# SparkFun_Qwiic_Mini_Human_Presence_Senso.net
KiCad netlist of a schematic drawn in EAGLE
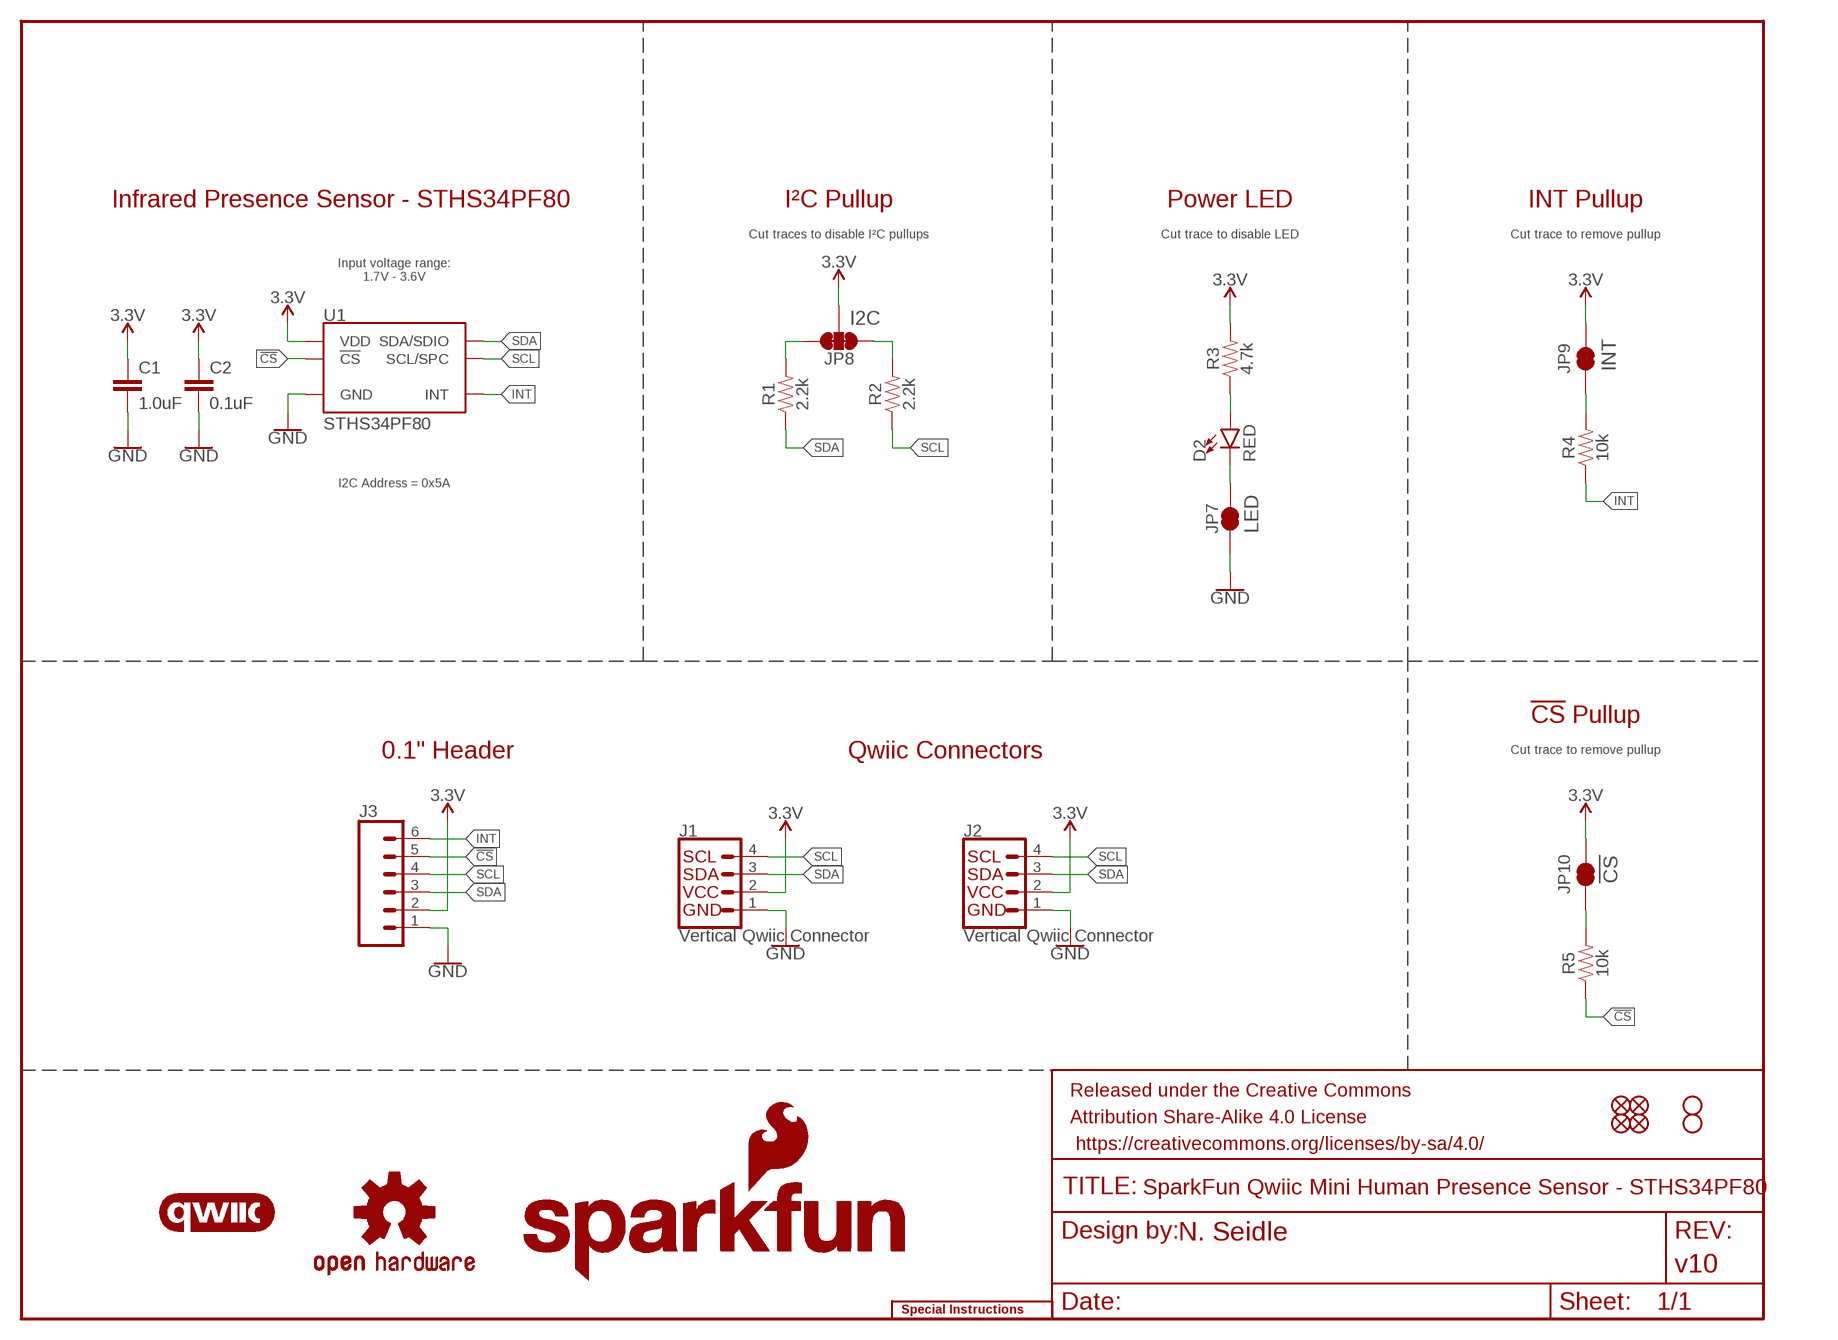
[diagram p0: schematic, sheet 1]

(export (version "E")
  (design (tool "Eeschema 10.0.6"))
  (components
    (comp (ref "C1")
      (value "1.0uF")
      (footprint "eagle-import:0603")
      (libsource (lib "eagle-import") (part "1.0UF-0603-16V-10%"))
    )
    (comp (ref "C2")
      (value "0.1uF")
      (footprint "eagle-import:0603")
      (libsource (lib "eagle-import") (part "0.1UF-0603-25V-(+80/-20%)"))
    )
    (comp (ref "D2")
      (value "RED")
      (footprint "eagle-import:LED-0603")
      (libsource (lib "eagle-import") (part "LED-RED_0603-KB"))
    )
    (comp (ref "FRAME1")
      (value "FRAME-LETTER")
      (footprint "eagle-import:CREATIVE_COMMONS")
      (fields (field (name "DESIGNER") "N. Seidle") (field (name "REV") "v10"))
      (libsource (lib "eagle-import") (part "FRAME-LETTER"))
    )
    (comp (ref "J1")
      (value "Vertical Qwiic Connector")
      (footprint "eagle-import:JST04_1MM_VERT")
      (libsource (lib "eagle-import") (part "QWIIC_CONNECTOR"))
    )
    (comp (ref "J2")
      (value "Vertical Qwiic Connector")
      (footprint "eagle-import:JST04_1MM_VERT")
      (libsource (lib "eagle-import") (part "QWIIC_CONNECTOR"))
    )
    (comp (ref "J3")
      (value "CONN_06NO_SILK_FEMALE_PTH")
      (footprint "eagle-import:1X06_NO_SILK")
      (libsource (lib "eagle-import") (part "CONN_06NO_SILK_FEMALE_PTH"))
    )
    (comp (ref "JP1")
      (value "FIDUCIALUFIDUCIAL")
      (footprint "eagle-import:FIDUCIAL-MICRO")
      (libsource (lib "eagle-import") (part "FIDUCIALUFIDUCIAL"))
    )
    (comp (ref "JP2")
      (value "FIDUCIALUFIDUCIAL")
      (footprint "eagle-import:FIDUCIAL-MICRO")
      (libsource (lib "eagle-import") (part "FIDUCIALUFIDUCIAL"))
    )
    (comp (ref "JP3")
      (value "STAND-OFF")
      (footprint "eagle-import:STAND-OFF")
      (libsource (lib "eagle-import") (part "STAND-OFF"))
    )
    (comp (ref "JP4")
      (value "STAND-OFF")
      (footprint "eagle-import:STAND-OFF")
      (libsource (lib "eagle-import") (part "STAND-OFF"))
    )
    (comp (ref "JP5")
      (value "FIDUCIALUFIDUCIAL")
      (footprint "eagle-import:FIDUCIAL-MICRO")
      (libsource (lib "eagle-import") (part "FIDUCIALUFIDUCIAL"))
    )
    (comp (ref "JP6")
      (value "FIDUCIALUFIDUCIAL")
      (footprint "eagle-import:FIDUCIAL-MICRO")
      (libsource (lib "eagle-import") (part "FIDUCIALUFIDUCIAL"))
    )
    (comp (ref "JP7")
      (value "JUMPER-SMT_2_NC_TRACE_SILK")
      (footprint "eagle-import:SMT-JUMPER_2_NC_TRACE_SILK")
      (libsource (lib "eagle-import") (part "JUMPER-SMT_2_NC_TRACE_SILK"))
    )
    (comp (ref "JP8")
      (value "JUMPER-SMT_3_2-NC_TRACE_SILK")
      (footprint "eagle-import:SMT-JUMPER_3_2-NC_TRACE_SILK")
      (libsource (lib "eagle-import") (part "JUMPER-SMT_3_2-NC_TRACE_SILK"))
    )
    (comp (ref "JP9")
      (value "JUMPER-SMT_2_NC_TRACE_SILK")
      (footprint "eagle-import:SMT-JUMPER_2_NC_TRACE_SILK")
      (libsource (lib "eagle-import") (part "JUMPER-SMT_2_NC_TRACE_SILK"))
    )
    (comp (ref "JP10")
      (value "JUMPER-SMT_2_NC_TRACE_SILK")
      (footprint "eagle-import:SMT-JUMPER_2_NC_TRACE_SILK")
      (libsource (lib "eagle-import") (part "JUMPER-SMT_2_NC_TRACE_SILK"))
    )
    (comp (ref "LOGO1")
      (value "OSHW-LOGOS")
      (footprint "eagle-import:OSHW-LOGO-S")
      (libsource (lib "eagle-import") (part "OSHW-LOGOS"))
    )
    (comp (ref "LOGO2")
      (value "SFE_LOGO_NAME_FLAME7_MM")
      (footprint "eagle-import:SFE_LOGO_NAME_FLAME_7MM")
      (libsource (lib "eagle-import") (part "SFE_LOGO_NAME_FLAME7_MM"))
    )
    (comp (ref "LOGO3")
      (value "QWIIC_LOGO_CONNECTOR")
      (footprint "eagle-import:QWIIC_5.5MM")
      (libsource (lib "eagle-import") (part "QWIIC_LOGO_CONNECTOR"))
    )
    (comp (ref "LOGO4")
      (value "SFE_LOGO_NAME5_MM")
      (footprint "eagle-import:SFE_LOGO_NAME_5MM")
      (libsource (lib "eagle-import") (part "SFE_LOGO_NAME5_MM"))
    )
    (comp (ref "LOGO5")
      (value "SPECIAL_INSTRUCTIONS-ORDERING")
      (footprint "eagle-import:ORDERING_INSTRUCTIONS")
      (libsource (lib "eagle-import") (part "SPECIAL_INSTRUCTIONS-ORDERING"))
    )
    (comp (ref "LOGO6")
      (value "SFE_LOGO_FLAME.1_INCH")
      (footprint "eagle-import:SFE_LOGO_FLAME_.1")
      (libsource (lib "eagle-import") (part "SFE_LOGO_FLAME.1_INCH"))
    )
    (comp (ref "R1")
      (value "2.2k")
      (footprint "eagle-import:0603")
      (libsource (lib "eagle-import") (part "2.2KOHM-0603-1/10W-1%"))
    )
    (comp (ref "R2")
      (value "2.2k")
      (footprint "eagle-import:0603")
      (libsource (lib "eagle-import") (part "2.2KOHM-0603-1/10W-1%"))
    )
    (comp (ref "R3")
      (value "4.7k")
      (footprint "eagle-import:0603")
      (libsource (lib "eagle-import") (part "4.7KOHM-0603-1/10W-1%"))
    )
    (comp (ref "R4")
      (value "10k")
      (footprint "eagle-import:0603")
      (libsource (lib "eagle-import") (part "10KOHM-0603-1/10W-1%"))
    )
    (comp (ref "R5")
      (value "10k")
      (footprint "eagle-import:0603")
      (libsource (lib "eagle-import") (part "10KOHM-0603-1/10W-1%"))
    )
    (comp (ref "U1")
      (value "STHS34PF80")
      (footprint "eagle-import:OLGA-10L")
      (fields (field (name "PROD_ID") "IC-19626"))
      (libsource (lib "eagle-import") (part "STHS34PF80"))
    )
  )
  (nets
    (net (code "1") (name "/~{CS}") (class "Default")
      (node (ref "J3") (pin "5") (pinfunction "5_5") (pintype "passive"))
      (node (ref "R5") (pin "1") (pinfunction "1_1") (pintype "passive"))
      (node (ref "U1") (pin "3") (pinfunction "~{CS}_3") (pintype "input"))
    )
    (net (code "2") (name "3.3V") (class "Default")
      (node (ref "C1") (pin "1") (pinfunction "1_1") (pintype "passive"))
      (node (ref "C2") (pin "1") (pinfunction "1_1") (pintype "passive"))
      (node (ref "J1") (pin "2") (pinfunction "2_2") (pintype "power_in"))
      (node (ref "J2") (pin "2") (pinfunction "2_2") (pintype "power_in"))
      (node (ref "J3") (pin "2") (pinfunction "2_2") (pintype "passive"))
      (node (ref "JP10") (pin "2") (pinfunction "2_2") (pintype "passive"))
      (node (ref "JP8") (pin "2") (pinfunction "2_2") (pintype "passive"))
      (node (ref "JP9") (pin "2") (pinfunction "2_2") (pintype "passive"))
      (node (ref "R3") (pin "2") (pinfunction "2_2") (pintype "passive"))
      (node (ref "U1") (pin "6") (pinfunction "VDD_6") (pintype "power_in"))
      (node (ref "U1") (pin "9") (pinfunction "VDD_9") (pintype "power_in"))
    )
    (net (code "3") (name "GND") (class "Default")
      (node (ref "C1") (pin "2") (pinfunction "2_2") (pintype "passive"))
      (node (ref "C2") (pin "2") (pinfunction "2_2") (pintype "passive"))
      (node (ref "J1") (pin "1") (pinfunction "1_1") (pintype "power_in"))
      (node (ref "J2") (pin "1") (pinfunction "1_1") (pintype "power_in"))
      (node (ref "J3") (pin "1") (pinfunction "1_1") (pintype "passive"))
      (node (ref "JP7") (pin "1") (pinfunction "1_1") (pintype "passive"))
      (node (ref "U1") (pin "2") (pinfunction "GND_2") (pintype "power_in"))
      (node (ref "U1") (pin "7") (pinfunction "GND_7") (pintype "power_in"))
      (node (ref "U1") (pin "8") (pinfunction "GND_8") (pintype "power_in"))
    )
    (net (code "4") (name "INT") (class "Default")
      (node (ref "J3") (pin "6") (pinfunction "6_6") (pintype "passive"))
      (node (ref "R4") (pin "1") (pinfunction "1_1") (pintype "passive"))
      (node (ref "U1") (pin "10") (pinfunction "INT_10") (pintype "output"))
    )
    (net (code "5") (name "Net-(D2-PadA)") (class "Default")
      (node (ref "D2") (pin "A") (pinfunction "A_A") (pintype "passive"))
      (node (ref "R3") (pin "1") (pinfunction "1_1") (pintype "passive"))
    )
    (net (code "6") (name "Net-(D2-PadC)") (class "Default")
      (node (ref "D2") (pin "C") (pinfunction "C_C") (pintype "passive"))
      (node (ref "JP7") (pin "2") (pinfunction "2_2") (pintype "passive"))
    )
    (net (code "7") (name "Net-(JP8-Pad1)") (class "Default")
      (node (ref "JP8") (pin "1") (pinfunction "1_1") (pintype "passive"))
      (node (ref "R2") (pin "2") (pinfunction "2_2") (pintype "passive"))
    )
    (net (code "8") (name "Net-(JP8-Pad3)") (class "Default")
      (node (ref "JP8") (pin "3") (pinfunction "3_3") (pintype "passive"))
      (node (ref "R1") (pin "2") (pinfunction "2_2") (pintype "passive"))
    )
    (net (code "9") (name "Net-(JP9-Pad1)") (class "Default")
      (node (ref "JP9") (pin "1") (pinfunction "1_1") (pintype "passive"))
      (node (ref "R4") (pin "2") (pinfunction "2_2") (pintype "passive"))
    )
    (net (code "10") (name "Net-(JP10-Pad1)") (class "Default")
      (node (ref "JP10") (pin "1") (pinfunction "1_1") (pintype "passive"))
      (node (ref "R5") (pin "2") (pinfunction "2_2") (pintype "passive"))
    )
    (net (code "11") (name "SCL") (class "Default")
      (node (ref "J1") (pin "4") (pinfunction "4_4") (pintype "passive"))
      (node (ref "J2") (pin "4") (pinfunction "4_4") (pintype "passive"))
      (node (ref "J3") (pin "4") (pinfunction "4_4") (pintype "passive"))
      (node (ref "R2") (pin "1") (pinfunction "1_1") (pintype "passive"))
      (node (ref "U1") (pin "1") (pinfunction "SCL/SPC_1") (pintype "bidirectional"))
    )
    (net (code "12") (name "SDA") (class "Default")
      (node (ref "J1") (pin "3") (pinfunction "3_3") (pintype "passive"))
      (node (ref "J2") (pin "3") (pinfunction "3_3") (pintype "passive"))
      (node (ref "J3") (pin "3") (pinfunction "3_3") (pintype "passive"))
      (node (ref "R1") (pin "1") (pinfunction "1_1") (pintype "passive"))
      (node (ref "U1") (pin "4") (pinfunction "SDA/SDIO_4") (pintype "bidirectional"))
    )
  )
)
